# preparedinstruments_0_bechemel_v10_KEYPA.net
KiCad netlist of a schematic drawn in EAGLE
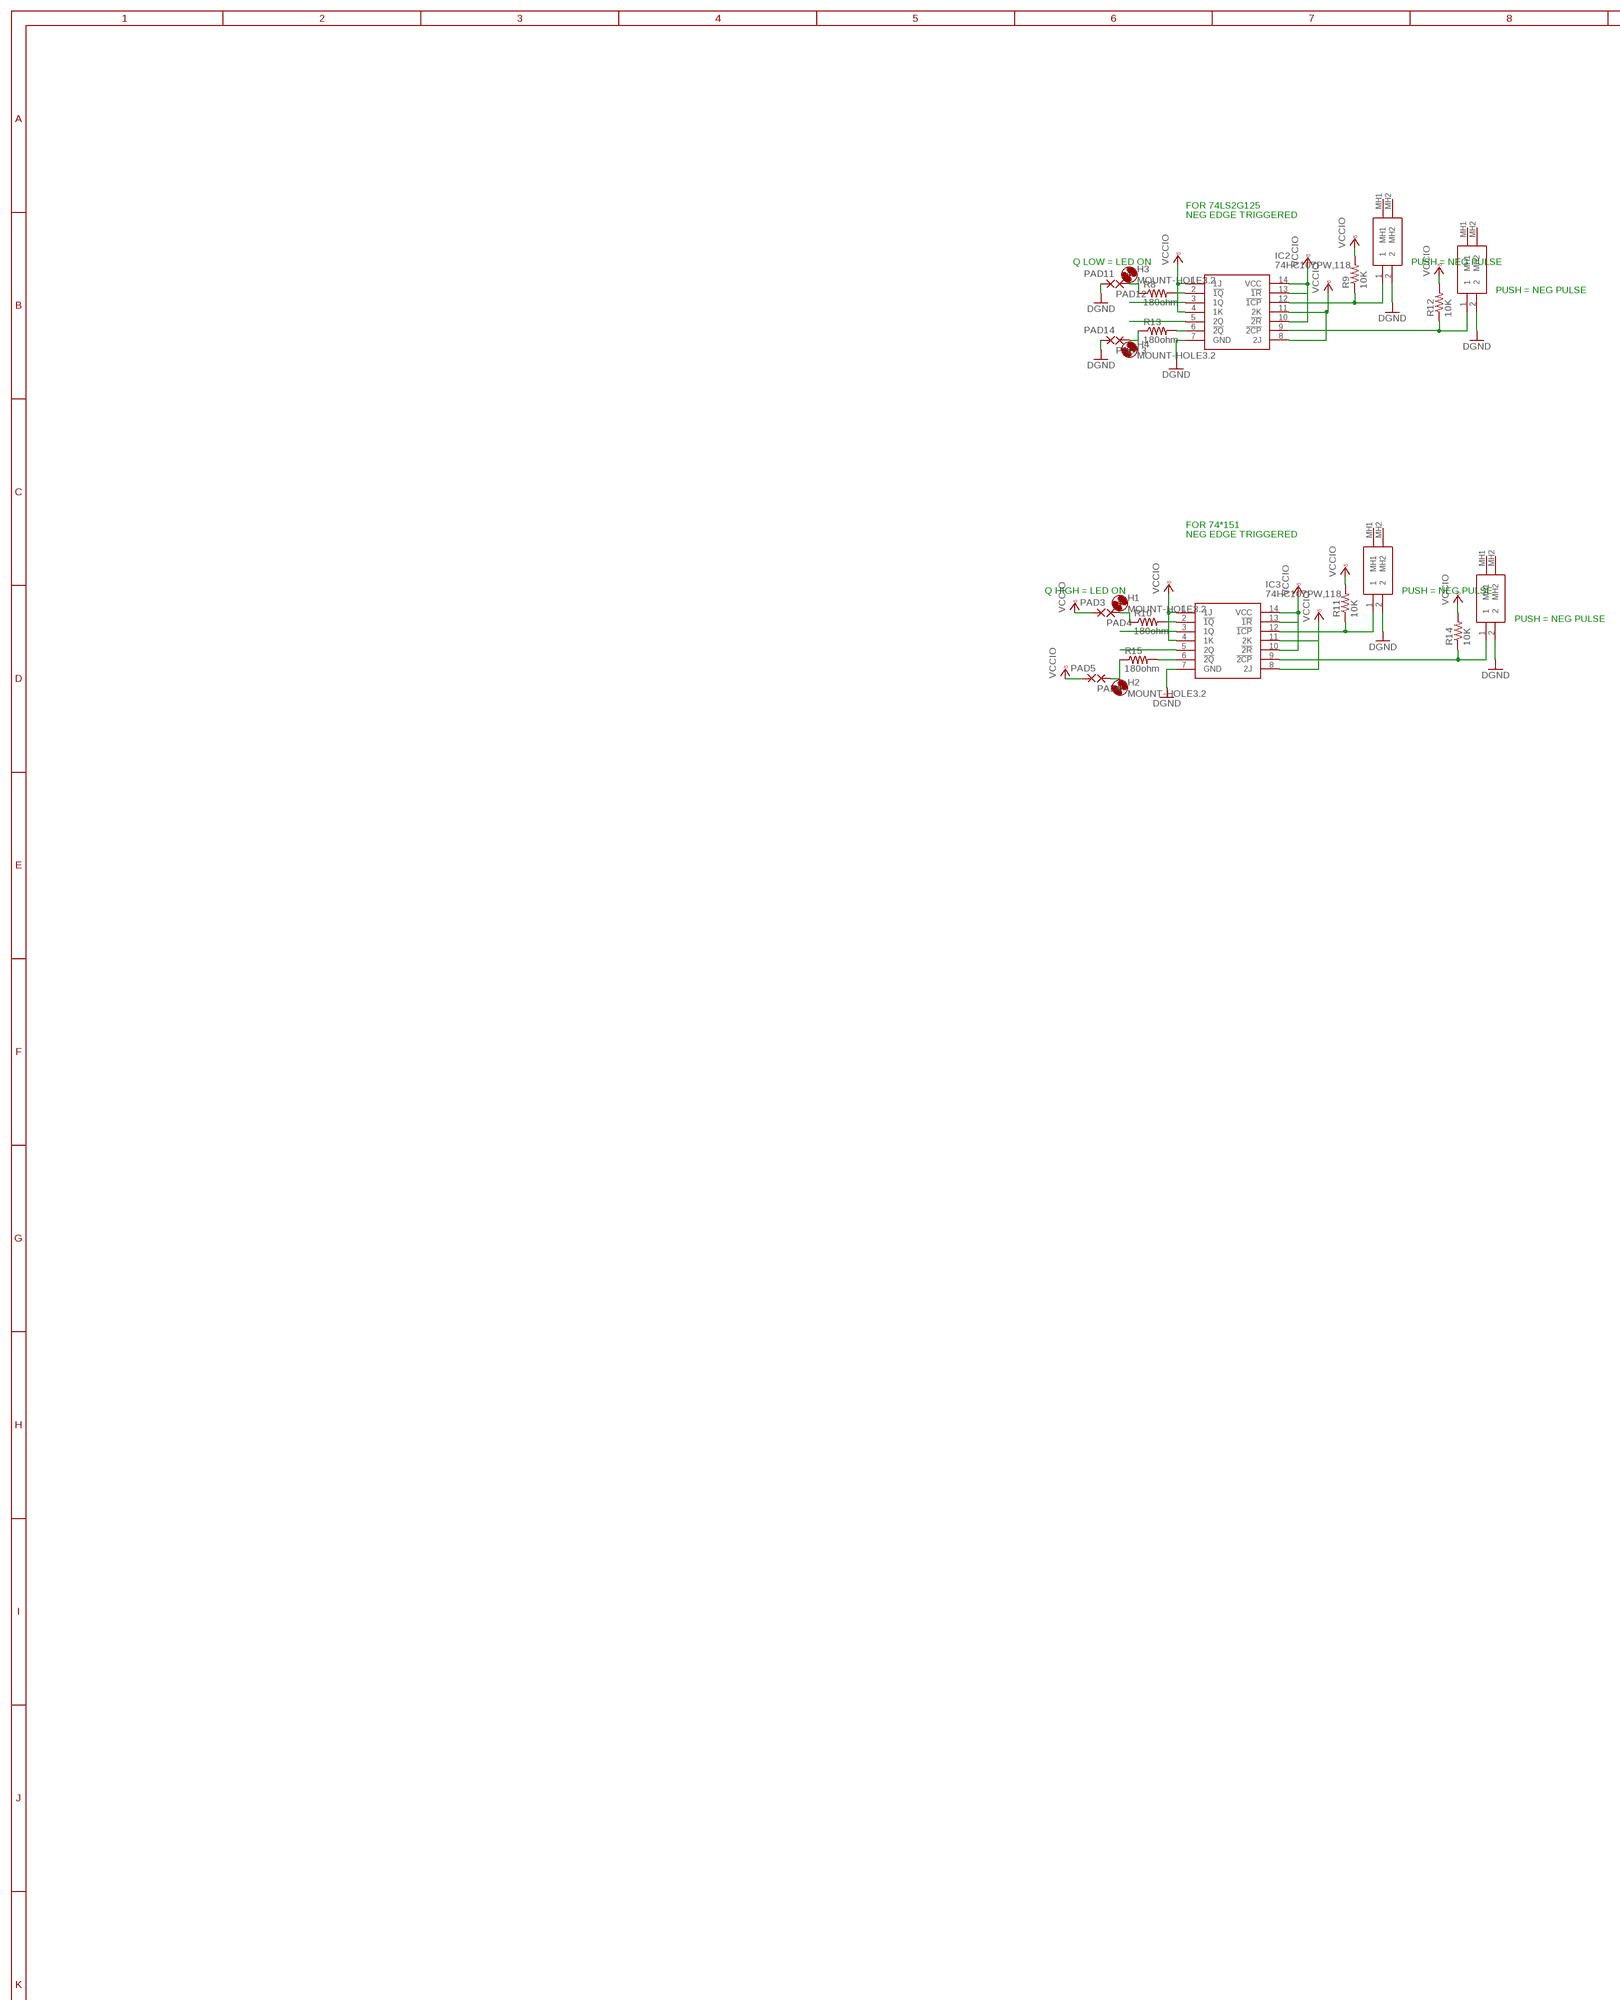
[diagram p0: schematic, sheet 1, part 1 of 3]
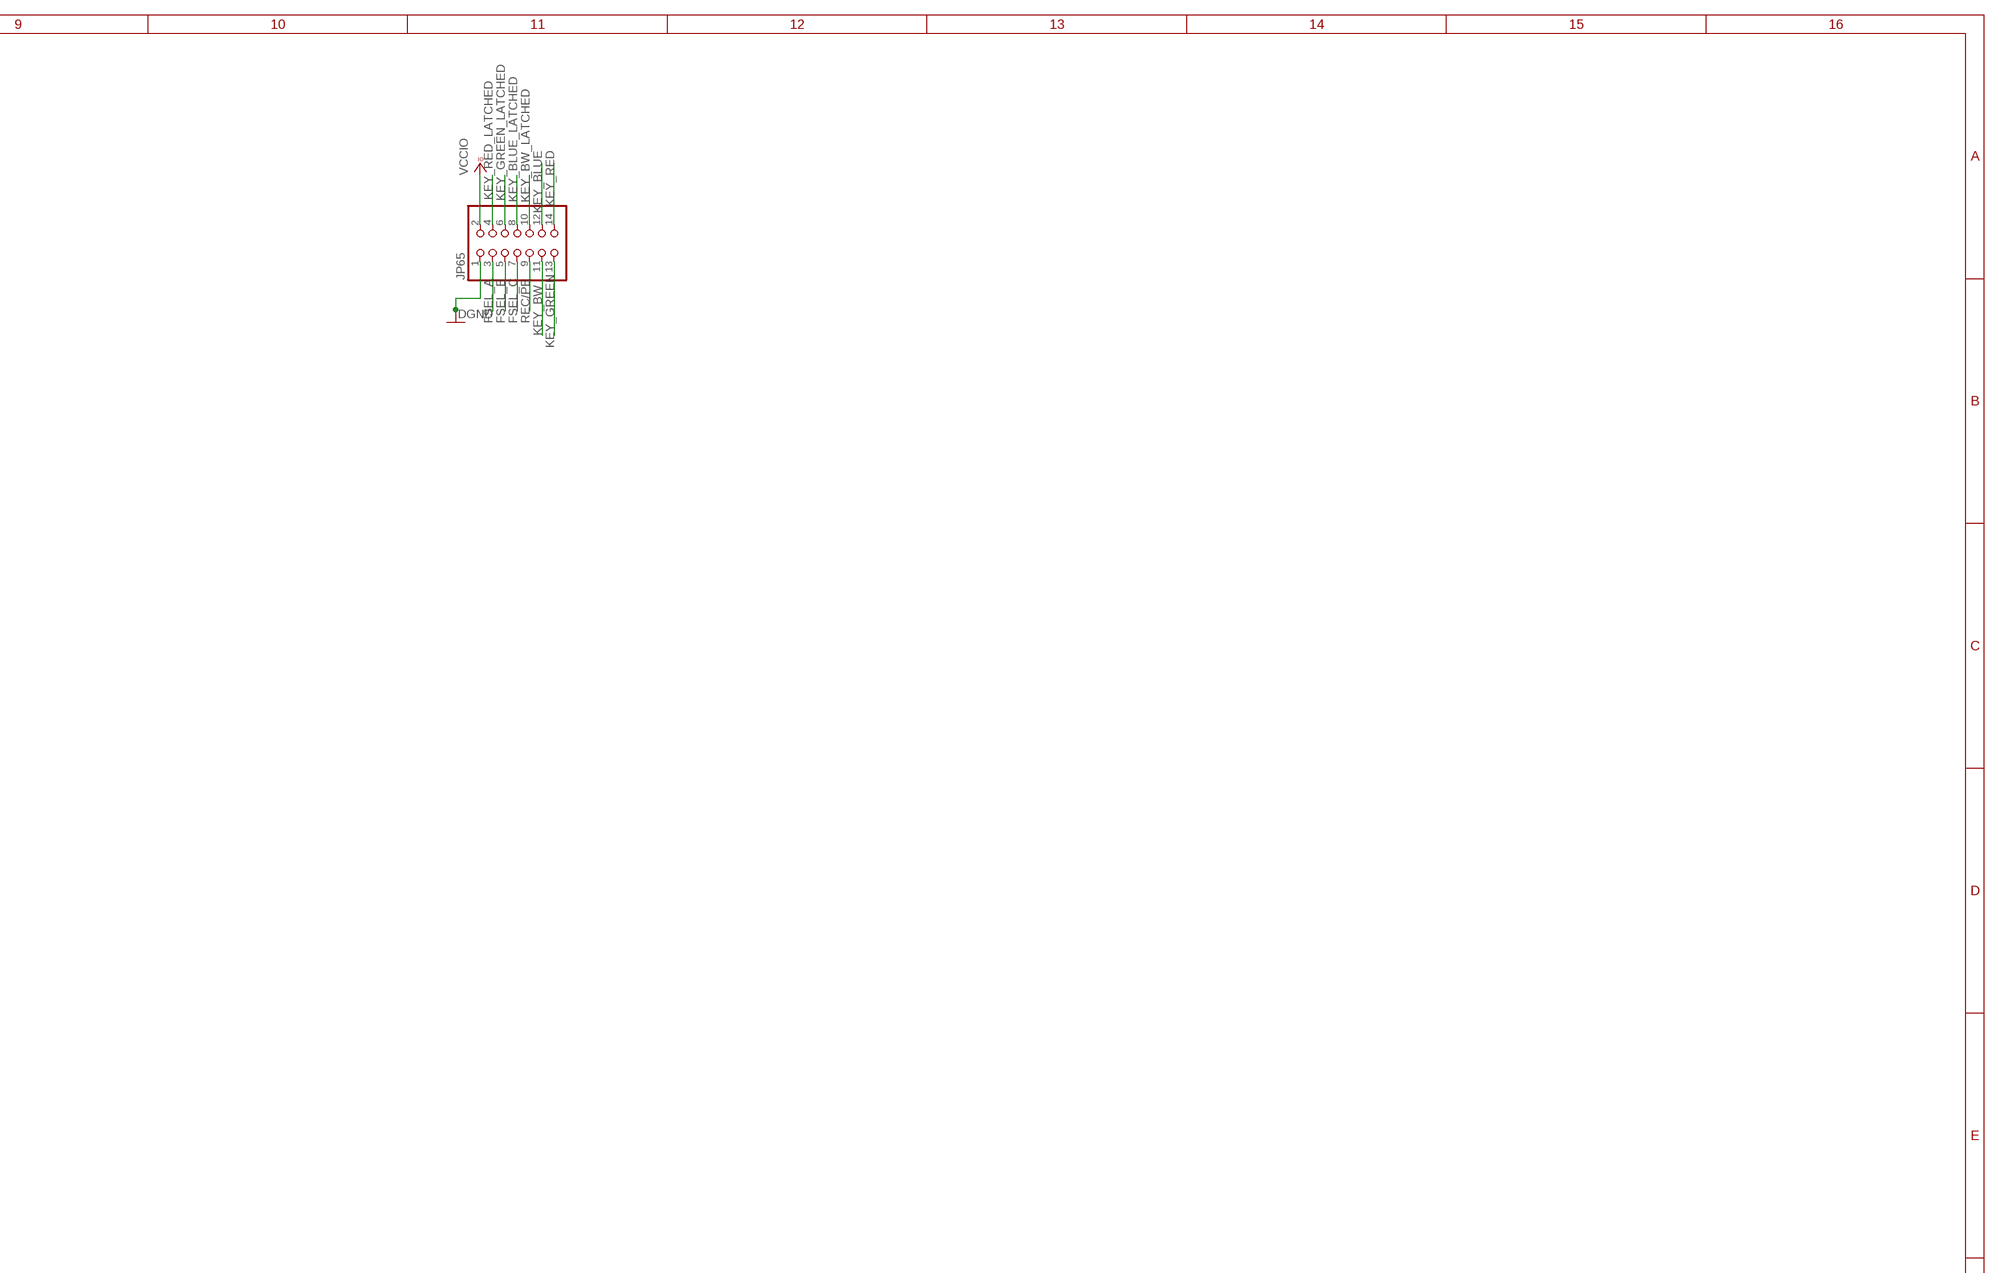
[diagram p1: schematic, sheet 1, part 2 of 3]
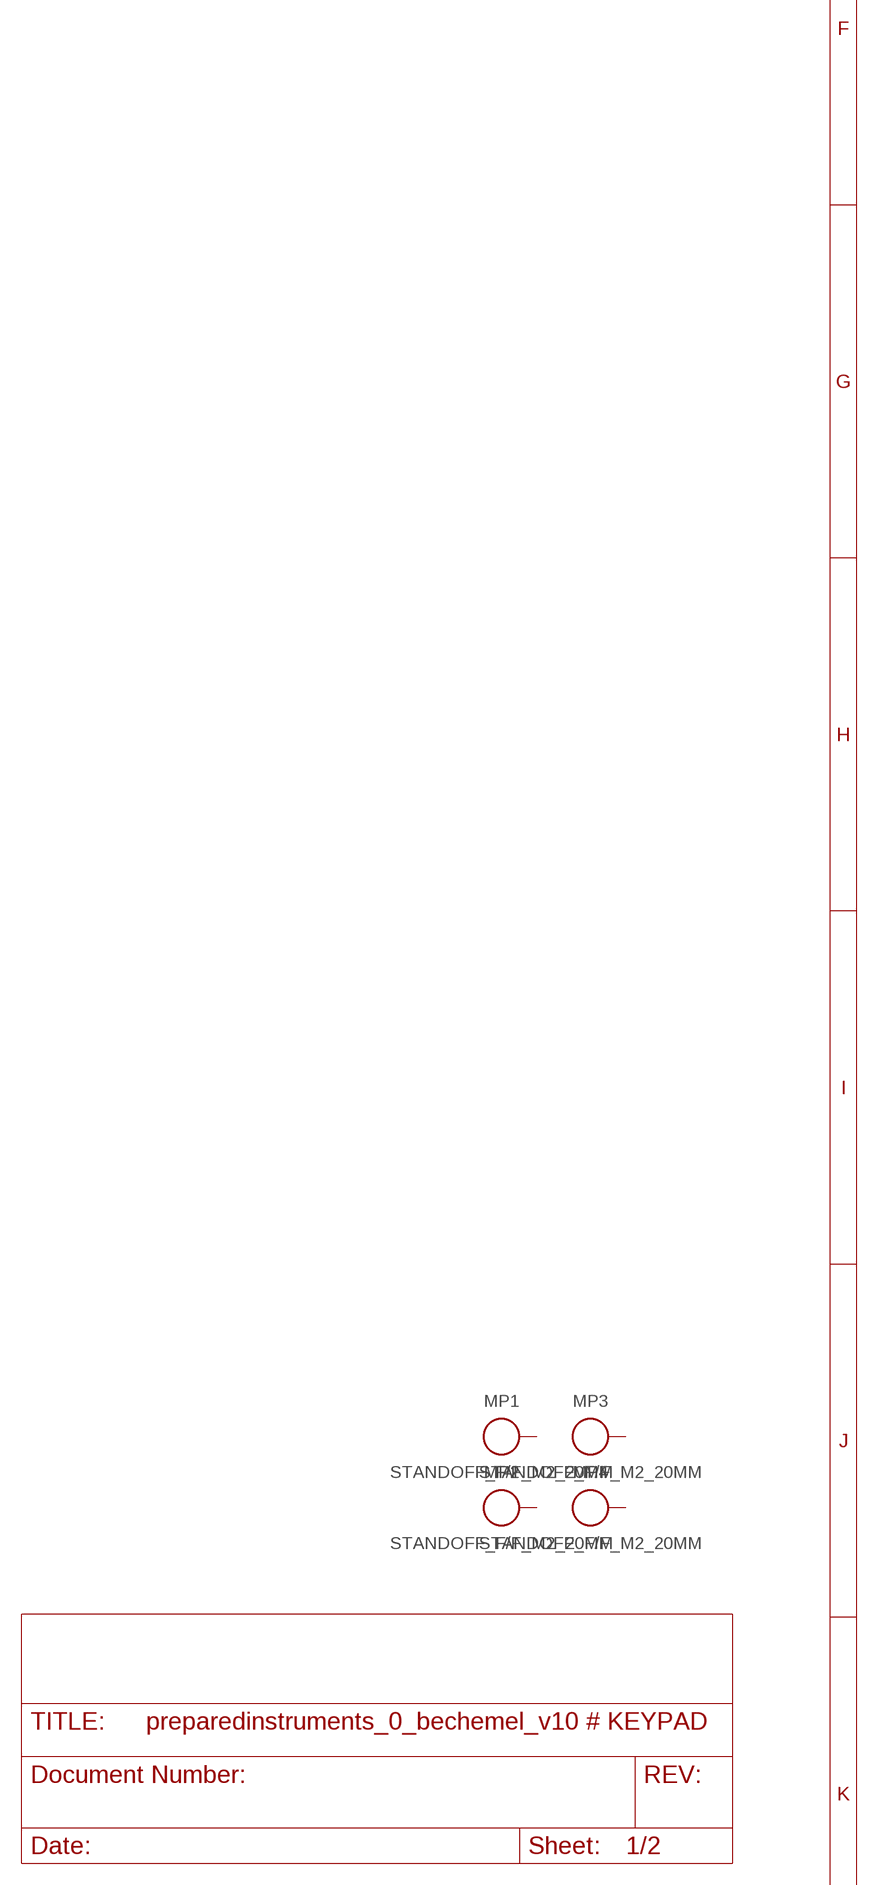
[diagram p2: schematic, sheet 1, part 3 of 3]
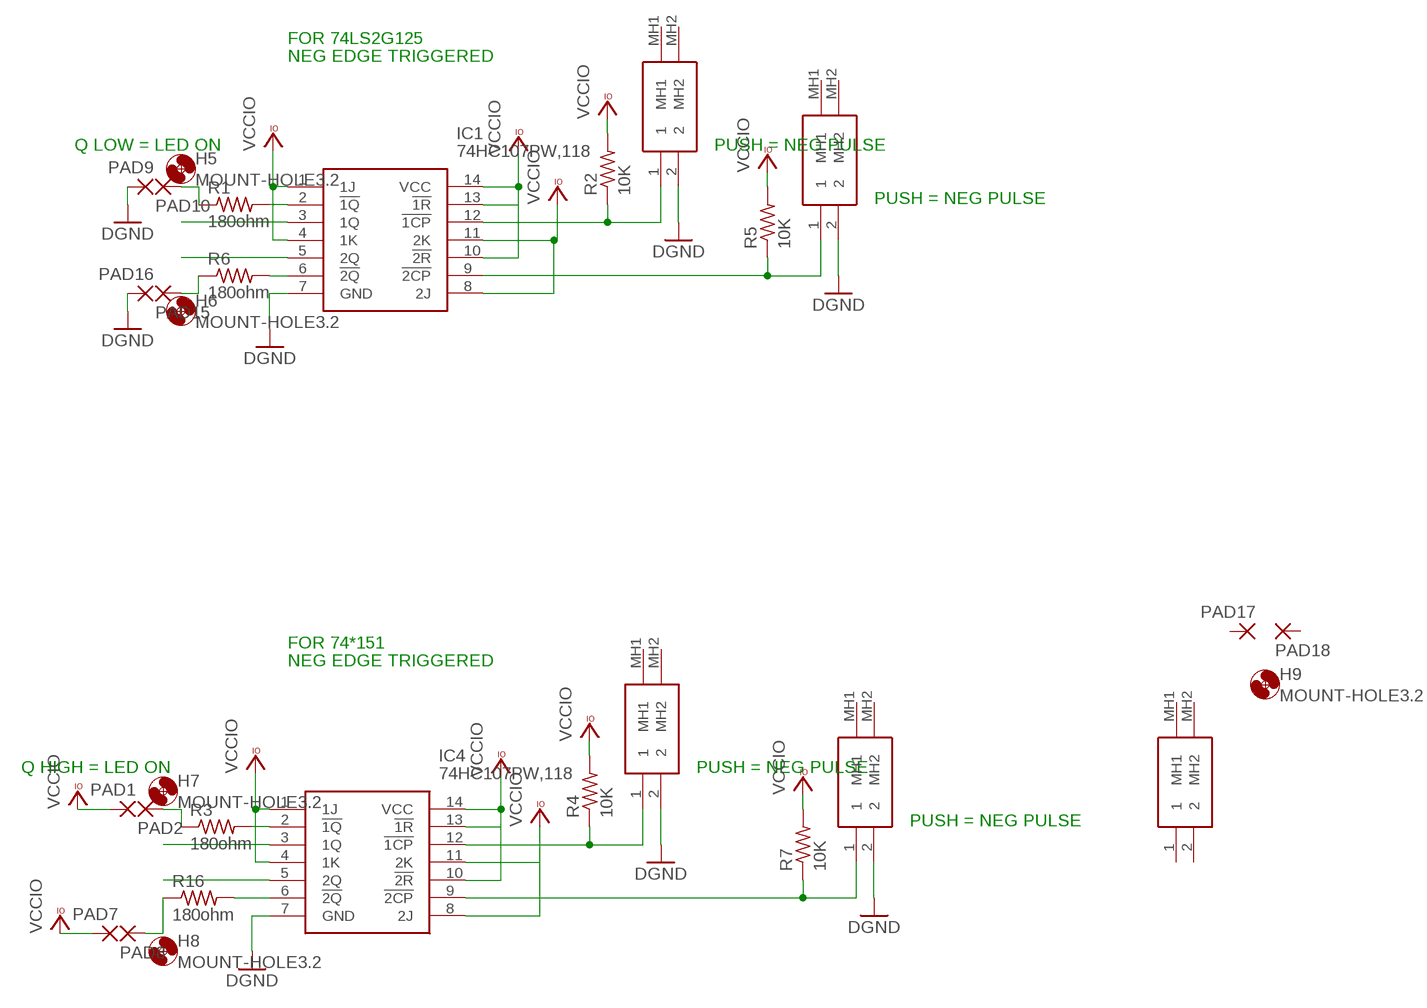
[diagram p3: schematic, sheet 2]

(export (version "E")
  (design (tool "Eeschema 10.0.6"))
  (components
    (comp (ref "H1")
      (value "MOUNT-HOLE3.2")
      (footprint "eagle-import:3,2")
      (libsource (lib "eagle-import") (part "MOUNT-HOLE3.2"))
    )
    (comp (ref "H2")
      (value "MOUNT-HOLE3.2")
      (footprint "eagle-import:3,2")
      (libsource (lib "eagle-import") (part "MOUNT-HOLE3.2"))
    )
    (comp (ref "H3")
      (value "MOUNT-HOLE3.2")
      (footprint "eagle-import:3,2")
      (libsource (lib "eagle-import") (part "MOUNT-HOLE3.2"))
    )
    (comp (ref "H4")
      (value "MOUNT-HOLE3.2")
      (footprint "eagle-import:3,2")
      (libsource (lib "eagle-import") (part "MOUNT-HOLE3.2"))
    )
    (comp (ref "IC2")
      (value "74HC107PW,118")
      (footprint "eagle-import:SOP65P640X110-14N")
      (fields (field (name "MOUSER_PART_NUMBER") "771-HC107PW118"))
      (libsource (lib "eagle-import") (part "74HC107PW,118"))
    )
    (comp (ref "IC3")
      (value "74HC107PW,118")
      (footprint "eagle-import:SOP65P640X110-14N")
      (fields (field (name "MOUSER_PART_NUMBER") "771-HC107PW118"))
      (libsource (lib "eagle-import") (part "74HC107PW,118"))
    )
    (comp (ref "JP65")
      (value "PINHD-2X7")
      (footprint "eagle-import:2X07")
      (libsource (lib "eagle-import") (part "PINHD-2X7"))
    )
    (comp (ref "MP1")
      (value "STANDOFF_F/F_M2_20MM")
      (footprint "eagle-import:STANDOFF_HEX_FEMALE_400X2000_M2X0.4_MTGP600H220")
      (libsource (lib "eagle-import") (part "STANDOFF_F/FM2_20MM_"))
    )
    (comp (ref "MP2")
      (value "STANDOFF_F/F_M2_20MM")
      (footprint "eagle-import:STANDOFF_HEX_FEMALE_400X2000_M2X0.4_MTGP600H220")
      (libsource (lib "eagle-import") (part "STANDOFF_F/FM2_20MM_"))
    )
    (comp (ref "MP3")
      (value "STANDOFF_F/F_M2_20MM")
      (footprint "eagle-import:STANDOFF_HEX_FEMALE_400X2000_M2X0.4_MTGP600H220")
      (libsource (lib "eagle-import") (part "STANDOFF_F/FM2_20MM_"))
    )
    (comp (ref "MP4")
      (value "STANDOFF_F/F_M2_20MM")
      (footprint "eagle-import:STANDOFF_HEX_FEMALE_400X2000_M2X0.4_MTGP600H220")
      (libsource (lib "eagle-import") (part "STANDOFF_F/FM2_20MM_"))
    )
    (comp (ref "PAD3")
      (value "SMD2")
      (footprint "eagle-import:SMD1,27-2,54")
      (libsource (lib "eagle-import") (part "SMD2"))
    )
    (comp (ref "PAD4")
      (value "SMD2")
      (footprint "eagle-import:SMD1,27-2,54")
      (libsource (lib "eagle-import") (part "SMD2"))
    )
    (comp (ref "PAD5")
      (value "SMD2")
      (footprint "eagle-import:SMD1,27-2,54")
      (libsource (lib "eagle-import") (part "SMD2"))
    )
    (comp (ref "PAD6")
      (value "SMD2")
      (footprint "eagle-import:SMD1,27-2,54")
      (libsource (lib "eagle-import") (part "SMD2"))
    )
    (comp (ref "PAD11")
      (value "SMD2")
      (footprint "eagle-import:SMD1,27-2,54")
      (libsource (lib "eagle-import") (part "SMD2"))
    )
    (comp (ref "PAD12")
      (value "SMD2")
      (footprint "eagle-import:SMD1,27-2,54")
      (libsource (lib "eagle-import") (part "SMD2"))
    )
    (comp (ref "PAD13")
      (value "SMD2")
      (footprint "eagle-import:SMD1,27-2,54")
      (libsource (lib "eagle-import") (part "SMD2"))
    )
    (comp (ref "PAD14")
      (value "SMD2")
      (footprint "eagle-import:SMD1,27-2,54")
      (libsource (lib "eagle-import") (part "SMD2"))
    )
    (comp (ref "R8")
      (value "180ohm")
      (footprint "eagle-import:R0805")
      (libsource (lib "eagle-import") (part "R-US_R0805"))
    )
    (comp (ref "R9")
      (value "10K")
      (footprint "eagle-import:R0805")
      (libsource (lib "eagle-import") (part "R-US_R0805"))
    )
    (comp (ref "R10")
      (value "180ohm")
      (footprint "eagle-import:R0805")
      (libsource (lib "eagle-import") (part "R-US_R0805"))
    )
    (comp (ref "R11")
      (value "10K")
      (footprint "eagle-import:R0805")
      (libsource (lib "eagle-import") (part "R-US_R0805"))
    )
    (comp (ref "R12")
      (value "10K")
      (footprint "eagle-import:R0805")
      (libsource (lib "eagle-import") (part "R-US_R0805"))
    )
    (comp (ref "R13")
      (value "180ohm")
      (footprint "eagle-import:R0805")
      (libsource (lib "eagle-import") (part "R-US_R0805"))
    )
    (comp (ref "R14")
      (value "10K")
      (footprint "eagle-import:R0805")
      (libsource (lib "eagle-import") (part "R-US_R0805"))
    )
    (comp (ref "R15")
      (value "180ohm")
      (footprint "eagle-import:R0805")
      (libsource (lib "eagle-import") (part "R-US_R0805"))
    )
    (comp (ref "S6")
      (value "MX1A-11NW")
      (footprint "eagle-import:MX1A11NW")
      (fields (field (name "MOUSER_PART_NUMBER") "540-MX1A-11NW"))
      (libsource (lib "eagle-import") (part "MX1A-11NW"))
    )
    (comp (ref "S7")
      (value "MX1A-11NW")
      (footprint "eagle-import:MX1A11NW")
      (fields (field (name "MOUSER_PART_NUMBER") "540-MX1A-11NW"))
      (libsource (lib "eagle-import") (part "MX1A-11NW"))
    )
    (comp (ref "S8")
      (value "MX1A-11NW")
      (footprint "eagle-import:MX1A11NW")
      (fields (field (name "MOUSER_PART_NUMBER") "540-MX1A-11NW"))
      (libsource (lib "eagle-import") (part "MX1A-11NW"))
    )
    (comp (ref "S9")
      (value "MX1A-11NW")
      (footprint "eagle-import:MX1A11NW")
      (fields (field (name "MOUSER_PART_NUMBER") "540-MX1A-11NW"))
      (libsource (lib "eagle-import") (part "MX1A-11NW"))
    )
    (comp (ref "H5")
      (value "MOUNT-HOLE3.2")
      (footprint "eagle-import:3,2")
      (libsource (lib "eagle-import") (part "MOUNT-HOLE3.2"))
    )
    (comp (ref "H6")
      (value "MOUNT-HOLE3.2")
      (footprint "eagle-import:3,2")
      (libsource (lib "eagle-import") (part "MOUNT-HOLE3.2"))
    )
    (comp (ref "H7")
      (value "MOUNT-HOLE3.2")
      (footprint "eagle-import:3,2")
      (libsource (lib "eagle-import") (part "MOUNT-HOLE3.2"))
    )
    (comp (ref "H8")
      (value "MOUNT-HOLE3.2")
      (footprint "eagle-import:3,2")
      (libsource (lib "eagle-import") (part "MOUNT-HOLE3.2"))
    )
    (comp (ref "H9")
      (value "MOUNT-HOLE3.2")
      (footprint "eagle-import:3,2")
      (libsource (lib "eagle-import") (part "MOUNT-HOLE3.2"))
    )
    (comp (ref "IC1")
      (value "74HC107PW,118")
      (footprint "eagle-import:SOP65P640X110-14N")
      (fields (field (name "MOUSER_PART_NUMBER") "771-HC107PW118"))
      (libsource (lib "eagle-import") (part "74HC107PW,118"))
    )
    (comp (ref "IC4")
      (value "74HC107PW,118")
      (footprint "eagle-import:SOP65P640X110-14N")
      (fields (field (name "MOUSER_PART_NUMBER") "771-HC107PW118"))
      (libsource (lib "eagle-import") (part "74HC107PW,118"))
    )
    (comp (ref "PAD1")
      (value "SMD2")
      (footprint "eagle-import:SMD1,27-2,54")
      (libsource (lib "eagle-import") (part "SMD2"))
    )
    (comp (ref "PAD2")
      (value "SMD2")
      (footprint "eagle-import:SMD1,27-2,54")
      (libsource (lib "eagle-import") (part "SMD2"))
    )
    (comp (ref "PAD7")
      (value "SMD2")
      (footprint "eagle-import:SMD1,27-2,54")
      (libsource (lib "eagle-import") (part "SMD2"))
    )
    (comp (ref "PAD8")
      (value "SMD2")
      (footprint "eagle-import:SMD1,27-2,54")
      (libsource (lib "eagle-import") (part "SMD2"))
    )
    (comp (ref "PAD9")
      (value "SMD2")
      (footprint "eagle-import:SMD1,27-2,54")
      (libsource (lib "eagle-import") (part "SMD2"))
    )
    (comp (ref "PAD10")
      (value "SMD2")
      (footprint "eagle-import:SMD1,27-2,54")
      (libsource (lib "eagle-import") (part "SMD2"))
    )
    (comp (ref "PAD15")
      (value "SMD2")
      (footprint "eagle-import:SMD1,27-2,54")
      (libsource (lib "eagle-import") (part "SMD2"))
    )
    (comp (ref "PAD16")
      (value "SMD2")
      (footprint "eagle-import:SMD1,27-2,54")
      (libsource (lib "eagle-import") (part "SMD2"))
    )
    (comp (ref "PAD17")
      (value "SMD2")
      (footprint "eagle-import:SMD1,27-2,54")
      (libsource (lib "eagle-import") (part "SMD2"))
    )
    (comp (ref "PAD18")
      (value "SMD2")
      (footprint "eagle-import:SMD1,27-2,54")
      (libsource (lib "eagle-import") (part "SMD2"))
    )
    (comp (ref "R1")
      (value "180ohm")
      (footprint "eagle-import:R0805")
      (libsource (lib "eagle-import") (part "R-US_R0805"))
    )
    (comp (ref "R2")
      (value "10K")
      (footprint "eagle-import:R0805")
      (libsource (lib "eagle-import") (part "R-US_R0805"))
    )
    (comp (ref "R3")
      (value "180ohm")
      (footprint "eagle-import:R0805")
      (libsource (lib "eagle-import") (part "R-US_R0805"))
    )
    (comp (ref "R4")
      (value "10K")
      (footprint "eagle-import:R0805")
      (libsource (lib "eagle-import") (part "R-US_R0805"))
    )
    (comp (ref "R5")
      (value "10K")
      (footprint "eagle-import:R0805")
      (libsource (lib "eagle-import") (part "R-US_R0805"))
    )
    (comp (ref "R6")
      (value "180ohm")
      (footprint "eagle-import:R0805")
      (libsource (lib "eagle-import") (part "R-US_R0805"))
    )
    (comp (ref "R7")
      (value "10K")
      (footprint "eagle-import:R0805")
      (libsource (lib "eagle-import") (part "R-US_R0805"))
    )
    (comp (ref "R16")
      (value "180ohm")
      (footprint "eagle-import:R0805")
      (libsource (lib "eagle-import") (part "R-US_R0805"))
    )
    (comp (ref "S1")
      (value "MX1A-11NW")
      (footprint "eagle-import:MX1A11NW")
      (fields (field (name "MOUSER_PART_NUMBER") "540-MX1A-11NW"))
      (libsource (lib "eagle-import") (part "MX1A-11NW"))
    )
    (comp (ref "S2")
      (value "MX1A-11NW")
      (footprint "eagle-import:MX1A11NW")
      (fields (field (name "MOUSER_PART_NUMBER") "540-MX1A-11NW"))
      (libsource (lib "eagle-import") (part "MX1A-11NW"))
    )
    (comp (ref "S3")
      (value "MX1A-11NW")
      (footprint "eagle-import:MX1A11NW")
      (fields (field (name "MOUSER_PART_NUMBER") "540-MX1A-11NW"))
      (libsource (lib "eagle-import") (part "MX1A-11NW"))
    )
    (comp (ref "S4")
      (value "MX1A-11NW")
      (footprint "eagle-import:MX1A11NW")
      (fields (field (name "MOUSER_PART_NUMBER") "540-MX1A-11NW"))
      (libsource (lib "eagle-import") (part "MX1A-11NW"))
    )
    (comp (ref "S5")
      (value "MX1A-11NW")
      (footprint "eagle-import:MX1A11NW")
      (fields (field (name "MOUSER_PART_NUMBER") "540-MX1A-11NW"))
      (libsource (lib "eagle-import") (part "MX1A-11NW"))
    )
  )
  (nets
    (net (code "1") (name "DGND") (class "Default")
      (node (ref "IC1") (pin "7") (pinfunction "GND_7") (pintype "bidirectional"))
      (node (ref "IC2") (pin "7") (pinfunction "GND_7") (pintype "bidirectional"))
      (node (ref "IC3") (pin "7") (pinfunction "GND_7") (pintype "bidirectional"))
      (node (ref "IC4") (pin "7") (pinfunction "GND_7") (pintype "bidirectional"))
      (node (ref "JP65") (pin "1") (pinfunction "1_1") (pintype "passive"))
      (node (ref "PAD11") (pin "1") (pinfunction "P_1") (pintype "passive"))
      (node (ref "PAD14") (pin "1") (pinfunction "P_1") (pintype "passive"))
      (node (ref "PAD16") (pin "1") (pinfunction "P_1") (pintype "passive"))
      (node (ref "PAD9") (pin "1") (pinfunction "P_1") (pintype "passive"))
      (node (ref "S1") (pin "2") (pinfunction "2_2") (pintype "bidirectional"))
      (node (ref "S2") (pin "2") (pinfunction "2_2") (pintype "bidirectional"))
      (node (ref "S3") (pin "2") (pinfunction "2_2") (pintype "bidirectional"))
      (node (ref "S4") (pin "2") (pinfunction "2_2") (pintype "bidirectional"))
      (node (ref "S6") (pin "2") (pinfunction "2_2") (pintype "bidirectional"))
      (node (ref "S7") (pin "2") (pinfunction "2_2") (pintype "bidirectional"))
      (node (ref "S8") (pin "2") (pinfunction "2_2") (pintype "bidirectional"))
      (node (ref "S9") (pin "2") (pinfunction "2_2") (pintype "bidirectional"))
    )
    (net (code "2") (name "FSEL_A") (class "Default")
      (node (ref "JP65") (pin "3") (pinfunction "3_3") (pintype "passive"))
    )
    (net (code "3") (name "FSEL_B") (class "Default")
      (node (ref "JP65") (pin "5") (pinfunction "5_5") (pintype "passive"))
    )
    (net (code "4") (name "FSEL_C") (class "Default")
      (node (ref "JP65") (pin "7") (pinfunction "7_7") (pintype "passive"))
    )
    (net (code "5") (name "KEY_BLUE") (class "Default")
      (node (ref "JP65") (pin "12") (pinfunction "12_12") (pintype "passive"))
    )
    (net (code "6") (name "KEY_BLUE_LATCHED") (class "Default")
      (node (ref "JP65") (pin "8") (pinfunction "8_8") (pintype "passive"))
    )
    (net (code "7") (name "KEY_BW") (class "Default")
      (node (ref "JP65") (pin "11") (pinfunction "11_11") (pintype "passive"))
    )
    (net (code "8") (name "KEY_BW_LATCHED") (class "Default")
      (node (ref "JP65") (pin "10") (pinfunction "10_10") (pintype "passive"))
    )
    (net (code "9") (name "KEY_GREEN") (class "Default")
      (node (ref "JP65") (pin "13") (pinfunction "13_13") (pintype "passive"))
    )
    (net (code "10") (name "KEY_GREEN_LATCHED") (class "Default")
      (node (ref "JP65") (pin "6") (pinfunction "6_6") (pintype "passive"))
    )
    (net (code "11") (name "KEY_RED") (class "Default")
      (node (ref "JP65") (pin "14") (pinfunction "14_14") (pintype "passive"))
    )
    (net (code "12") (name "KEY_RED_LATCHED") (class "Default")
      (node (ref "JP65") (pin "4") (pinfunction "4_4") (pintype "passive"))
    )
    (net (code "13") (name "Net-(IC1-~{1CP})") (class "Default")
      (node (ref "IC1") (pin "12") (pinfunction "~{1CP}_12") (pintype "bidirectional"))
      (node (ref "R2") (pin "1") (pinfunction "1_1") (pintype "passive"))
      (node (ref "S1") (pin "1") (pinfunction "1_1") (pintype "bidirectional"))
    )
    (net (code "14") (name "Net-(IC1-~{1Q})") (class "Default")
      (node (ref "IC1") (pin "2") (pinfunction "~{1Q}_2") (pintype "bidirectional"))
      (node (ref "R1") (pin "2") (pinfunction "2_2") (pintype "passive"))
    )
    (net (code "15") (name "Net-(IC1-~{2CP})") (class "Default")
      (node (ref "IC1") (pin "9") (pinfunction "~{2CP}_9") (pintype "bidirectional"))
      (node (ref "R5") (pin "1") (pinfunction "1_1") (pintype "passive"))
      (node (ref "S3") (pin "1") (pinfunction "1_1") (pintype "bidirectional"))
    )
    (net (code "16") (name "Net-(IC1-~{2Q})") (class "Default")
      (node (ref "IC1") (pin "6") (pinfunction "~{2Q}_6") (pintype "bidirectional"))
      (node (ref "R6") (pin "2") (pinfunction "2_2") (pintype "passive"))
    )
    (net (code "17") (name "Net-(IC2-~{1CP})") (class "Default")
      (node (ref "IC2") (pin "12") (pinfunction "~{1CP}_12") (pintype "bidirectional"))
      (node (ref "R9") (pin "1") (pinfunction "1_1") (pintype "passive"))
      (node (ref "S6") (pin "1") (pinfunction "1_1") (pintype "bidirectional"))
    )
    (net (code "18") (name "Net-(IC2-~{1Q})") (class "Default")
      (node (ref "IC2") (pin "2") (pinfunction "~{1Q}_2") (pintype "bidirectional"))
      (node (ref "R8") (pin "2") (pinfunction "2_2") (pintype "passive"))
    )
    (net (code "19") (name "Net-(IC2-~{2CP})") (class "Default")
      (node (ref "IC2") (pin "9") (pinfunction "~{2CP}_9") (pintype "bidirectional"))
      (node (ref "R12") (pin "1") (pinfunction "1_1") (pintype "passive"))
      (node (ref "S8") (pin "1") (pinfunction "1_1") (pintype "bidirectional"))
    )
    (net (code "20") (name "Net-(IC2-~{2Q})") (class "Default")
      (node (ref "IC2") (pin "6") (pinfunction "~{2Q}_6") (pintype "bidirectional"))
      (node (ref "R13") (pin "2") (pinfunction "2_2") (pintype "passive"))
    )
    (net (code "21") (name "Net-(IC3-~{1CP})") (class "Default")
      (node (ref "IC3") (pin "12") (pinfunction "~{1CP}_12") (pintype "bidirectional"))
      (node (ref "R11") (pin "1") (pinfunction "1_1") (pintype "passive"))
      (node (ref "S7") (pin "1") (pinfunction "1_1") (pintype "bidirectional"))
    )
    (net (code "22") (name "Net-(IC3-~{1Q})") (class "Default")
      (node (ref "IC3") (pin "2") (pinfunction "~{1Q}_2") (pintype "bidirectional"))
      (node (ref "R10") (pin "2") (pinfunction "2_2") (pintype "passive"))
    )
    (net (code "23") (name "Net-(IC3-~{2CP})") (class "Default")
      (node (ref "IC3") (pin "9") (pinfunction "~{2CP}_9") (pintype "bidirectional"))
      (node (ref "R14") (pin "1") (pinfunction "1_1") (pintype "passive"))
      (node (ref "S9") (pin "1") (pinfunction "1_1") (pintype "bidirectional"))
    )
    (net (code "24") (name "Net-(IC3-~{2Q})") (class "Default")
      (node (ref "IC3") (pin "6") (pinfunction "~{2Q}_6") (pintype "bidirectional"))
      (node (ref "R15") (pin "2") (pinfunction "2_2") (pintype "passive"))
    )
    (net (code "25") (name "Net-(IC4-~{1CP})") (class "Default")
      (node (ref "IC4") (pin "12") (pinfunction "~{1CP}_12") (pintype "bidirectional"))
      (node (ref "R4") (pin "1") (pinfunction "1_1") (pintype "passive"))
      (node (ref "S2") (pin "1") (pinfunction "1_1") (pintype "bidirectional"))
    )
    (net (code "26") (name "Net-(IC4-~{1Q})") (class "Default")
      (node (ref "IC4") (pin "2") (pinfunction "~{1Q}_2") (pintype "bidirectional"))
      (node (ref "R3") (pin "2") (pinfunction "2_2") (pintype "passive"))
    )
    (net (code "27") (name "Net-(IC4-~{2CP})") (class "Default")
      (node (ref "IC4") (pin "9") (pinfunction "~{2CP}_9") (pintype "bidirectional"))
      (node (ref "R7") (pin "1") (pinfunction "1_1") (pintype "passive"))
      (node (ref "S4") (pin "1") (pinfunction "1_1") (pintype "bidirectional"))
    )
    (net (code "28") (name "Net-(IC4-~{2Q})") (class "Default")
      (node (ref "IC4") (pin "6") (pinfunction "~{2Q}_6") (pintype "bidirectional"))
      (node (ref "R16") (pin "2") (pinfunction "2_2") (pintype "passive"))
    )
    (net (code "29") (name "Net-(PAD2-P)") (class "Default")
      (node (ref "PAD2") (pin "1") (pinfunction "P_1") (pintype "passive"))
      (node (ref "R3") (pin "1") (pinfunction "1_1") (pintype "passive"))
    )
    (net (code "30") (name "Net-(PAD4-P)") (class "Default")
      (node (ref "PAD4") (pin "1") (pinfunction "P_1") (pintype "passive"))
      (node (ref "R10") (pin "1") (pinfunction "1_1") (pintype "passive"))
    )
    (net (code "31") (name "Net-(PAD6-P)") (class "Default")
      (node (ref "PAD6") (pin "1") (pinfunction "P_1") (pintype "passive"))
      (node (ref "R15") (pin "1") (pinfunction "1_1") (pintype "passive"))
    )
    (net (code "32") (name "Net-(PAD8-P)") (class "Default")
      (node (ref "PAD8") (pin "1") (pinfunction "P_1") (pintype "passive"))
      (node (ref "R16") (pin "1") (pinfunction "1_1") (pintype "passive"))
    )
    (net (code "33") (name "Net-(PAD10-P)") (class "Default")
      (node (ref "PAD10") (pin "1") (pinfunction "P_1") (pintype "passive"))
      (node (ref "R1") (pin "1") (pinfunction "1_1") (pintype "passive"))
    )
    (net (code "34") (name "Net-(PAD12-P)") (class "Default")
      (node (ref "PAD12") (pin "1") (pinfunction "P_1") (pintype "passive"))
      (node (ref "R8") (pin "1") (pinfunction "1_1") (pintype "passive"))
    )
    (net (code "35") (name "Net-(PAD13-P)") (class "Default")
      (node (ref "PAD13") (pin "1") (pinfunction "P_1") (pintype "passive"))
      (node (ref "R13") (pin "1") (pinfunction "1_1") (pintype "passive"))
    )
    (net (code "36") (name "Net-(PAD15-P)") (class "Default")
      (node (ref "PAD15") (pin "1") (pinfunction "P_1") (pintype "passive"))
      (node (ref "R6") (pin "1") (pinfunction "1_1") (pintype "passive"))
    )
    (net (code "37") (name "REC{slash}PB") (class "Default")
      (node (ref "JP65") (pin "9") (pinfunction "9_9") (pintype "passive"))
    )
    (net (code "38") (name "VCCIO") (class "Default")
      (node (ref "IC1") (pin "1") (pinfunction "1J_1") (pintype "bidirectional"))
      (node (ref "IC1") (pin "10") (pinfunction "~{2R}_10") (pintype "bidirectional"))
      (node (ref "IC1") (pin "11") (pinfunction "2K_11") (pintype "bidirectional"))
      (node (ref "IC1") (pin "13") (pinfunction "~{1R}_13") (pintype "bidirectional"))
      (node (ref "IC1") (pin "14") (pinfunction "VCC_14") (pintype "bidirectional"))
      (node (ref "IC1") (pin "4") (pinfunction "1K_4") (pintype "bidirectional"))
      (node (ref "IC1") (pin "8") (pinfunction "2J_8") (pintype "bidirectional"))
      (node (ref "IC2") (pin "1") (pinfunction "1J_1") (pintype "bidirectional"))
      (node (ref "IC2") (pin "10") (pinfunction "~{2R}_10") (pintype "bidirectional"))
      (node (ref "IC2") (pin "11") (pinfunction "2K_11") (pintype "bidirectional"))
      (node (ref "IC2") (pin "13") (pinfunction "~{1R}_13") (pintype "bidirectional"))
      (node (ref "IC2") (pin "14") (pinfunction "VCC_14") (pintype "bidirectional"))
      (node (ref "IC2") (pin "4") (pinfunction "1K_4") (pintype "bidirectional"))
      (node (ref "IC2") (pin "8") (pinfunction "2J_8") (pintype "bidirectional"))
      (node (ref "IC3") (pin "1") (pinfunction "1J_1") (pintype "bidirectional"))
      (node (ref "IC3") (pin "10") (pinfunction "~{2R}_10") (pintype "bidirectional"))
      (node (ref "IC3") (pin "11") (pinfunction "2K_11") (pintype "bidirectional"))
      (node (ref "IC3") (pin "13") (pinfunction "~{1R}_13") (pintype "bidirectional"))
      (node (ref "IC3") (pin "14") (pinfunction "VCC_14") (pintype "bidirectional"))
      (node (ref "IC3") (pin "4") (pinfunction "1K_4") (pintype "bidirectional"))
      (node (ref "IC3") (pin "8") (pinfunction "2J_8") (pintype "bidirectional"))
      (node (ref "IC4") (pin "1") (pinfunction "1J_1") (pintype "bidirectional"))
      (node (ref "IC4") (pin "10") (pinfunction "~{2R}_10") (pintype "bidirectional"))
      (node (ref "IC4") (pin "11") (pinfunction "2K_11") (pintype "bidirectional"))
      (node (ref "IC4") (pin "13") (pinfunction "~{1R}_13") (pintype "bidirectional"))
      (node (ref "IC4") (pin "14") (pinfunction "VCC_14") (pintype "bidirectional"))
      (node (ref "IC4") (pin "4") (pinfunction "1K_4") (pintype "bidirectional"))
      (node (ref "IC4") (pin "8") (pinfunction "2J_8") (pintype "bidirectional"))
      (node (ref "JP65") (pin "2") (pinfunction "2_2") (pintype "passive"))
      (node (ref "PAD1") (pin "1") (pinfunction "P_1") (pintype "passive"))
      (node (ref "PAD3") (pin "1") (pinfunction "P_1") (pintype "passive"))
      (node (ref "PAD5") (pin "1") (pinfunction "P_1") (pintype "passive"))
      (node (ref "PAD7") (pin "1") (pinfunction "P_1") (pintype "passive"))
      (node (ref "R11") (pin "2") (pinfunction "2_2") (pintype "passive"))
      (node (ref "R12") (pin "2") (pinfunction "2_2") (pintype "passive"))
      (node (ref "R14") (pin "2") (pinfunction "2_2") (pintype "passive"))
      (node (ref "R2") (pin "2") (pinfunction "2_2") (pintype "passive"))
      (node (ref "R4") (pin "2") (pinfunction "2_2") (pintype "passive"))
      (node (ref "R5") (pin "2") (pinfunction "2_2") (pintype "passive"))
      (node (ref "R7") (pin "2") (pinfunction "2_2") (pintype "passive"))
      (node (ref "R9") (pin "2") (pinfunction "2_2") (pintype "passive"))
    )
    (net (code "39") (name "unconnected-(IC1-1Q-Pad3)") (class "Default")
      (node (ref "IC1") (pin "3") (pinfunction "1Q_3") (pintype "bidirectional"))
    )
    (net (code "40") (name "unconnected-(IC1-2Q-Pad5)") (class "Default")
      (node (ref "IC1") (pin "5") (pinfunction "2Q_5") (pintype "bidirectional"))
    )
    (net (code "41") (name "unconnected-(IC2-1Q-Pad3)") (class "Default")
      (node (ref "IC2") (pin "3") (pinfunction "1Q_3") (pintype "bidirectional"))
    )
    (net (code "42") (name "unconnected-(IC2-2Q-Pad5)") (class "Default")
      (node (ref "IC2") (pin "5") (pinfunction "2Q_5") (pintype "bidirectional"))
    )
    (net (code "43") (name "unconnected-(IC3-1Q-Pad3)") (class "Default")
      (node (ref "IC3") (pin "3") (pinfunction "1Q_3") (pintype "bidirectional"))
    )
    (net (code "44") (name "unconnected-(IC3-2Q-Pad5)") (class "Default")
      (node (ref "IC3") (pin "5") (pinfunction "2Q_5") (pintype "bidirectional"))
    )
    (net (code "45") (name "unconnected-(IC4-1Q-Pad3)") (class "Default")
      (node (ref "IC4") (pin "3") (pinfunction "1Q_3") (pintype "bidirectional"))
    )
    (net (code "46") (name "unconnected-(IC4-2Q-Pad5)") (class "Default")
      (node (ref "IC4") (pin "5") (pinfunction "2Q_5") (pintype "bidirectional"))
    )
    (net (code "47") (name "unconnected-(MP1-P$1-Pad1)") (class "Default")
      (node (ref "MP1") (pin "1") (pinfunction "P$1_1") (pintype "passive"))
    )
    (net (code "48") (name "unconnected-(MP2-P$1-Pad1)") (class "Default")
      (node (ref "MP2") (pin "1") (pinfunction "P$1_1") (pintype "passive"))
    )
    (net (code "49") (name "unconnected-(MP3-P$1-Pad1)") (class "Default")
      (node (ref "MP3") (pin "1") (pinfunction "P$1_1") (pintype "passive"))
    )
    (net (code "50") (name "unconnected-(MP4-P$1-Pad1)") (class "Default")
      (node (ref "MP4") (pin "1") (pinfunction "P$1_1") (pintype "passive"))
    )
    (net (code "51") (name "unconnected-(PAD17-P-Pad1)") (class "Default")
      (node (ref "PAD17") (pin "1") (pinfunction "P_1") (pintype "passive"))
    )
    (net (code "52") (name "unconnected-(PAD18-P-Pad1)") (class "Default")
      (node (ref "PAD18") (pin "1") (pinfunction "P_1") (pintype "passive"))
    )
    (net (code "53") (name "unconnected-(S1-PadMH1)") (class "Default")
      (node (ref "S1") (pin "MH1") (pinfunction "MH1_MH1") (pintype "bidirectional"))
    )
    (net (code "54") (name "unconnected-(S1-PadMH2)") (class "Default")
      (node (ref "S1") (pin "MH2") (pinfunction "MH2_MH2") (pintype "bidirectional"))
    )
    (net (code "55") (name "unconnected-(S2-PadMH1)") (class "Default")
      (node (ref "S2") (pin "MH1") (pinfunction "MH1_MH1") (pintype "bidirectional"))
    )
    (net (code "56") (name "unconnected-(S2-PadMH2)") (class "Default")
      (node (ref "S2") (pin "MH2") (pinfunction "MH2_MH2") (pintype "bidirectional"))
    )
    (net (code "57") (name "unconnected-(S3-PadMH1)") (class "Default")
      (node (ref "S3") (pin "MH1") (pinfunction "MH1_MH1") (pintype "bidirectional"))
    )
    (net (code "58") (name "unconnected-(S3-PadMH2)") (class "Default")
      (node (ref "S3") (pin "MH2") (pinfunction "MH2_MH2") (pintype "bidirectional"))
    )
    (net (code "59") (name "unconnected-(S4-PadMH1)") (class "Default")
      (node (ref "S4") (pin "MH1") (pinfunction "MH1_MH1") (pintype "bidirectional"))
    )
    (net (code "60") (name "unconnected-(S4-PadMH2)") (class "Default")
      (node (ref "S4") (pin "MH2") (pinfunction "MH2_MH2") (pintype "bidirectional"))
    )
    (net (code "61") (name "unconnected-(S5-Pad1)") (class "Default")
      (node (ref "S5") (pin "1") (pinfunction "1_1") (pintype "bidirectional"))
    )
    (net (code "62") (name "unconnected-(S5-Pad2)") (class "Default")
      (node (ref "S5") (pin "2") (pinfunction "2_2") (pintype "bidirectional"))
    )
    (net (code "63") (name "unconnected-(S5-PadMH1)") (class "Default")
      (node (ref "S5") (pin "MH1") (pinfunction "MH1_MH1") (pintype "bidirectional"))
    )
    (net (code "64") (name "unconnected-(S5-PadMH2)") (class "Default")
      (node (ref "S5") (pin "MH2") (pinfunction "MH2_MH2") (pintype "bidirectional"))
    )
    (net (code "65") (name "unconnected-(S6-PadMH1)") (class "Default")
      (node (ref "S6") (pin "MH1") (pinfunction "MH1_MH1") (pintype "bidirectional"))
    )
    (net (code "66") (name "unconnected-(S6-PadMH2)") (class "Default")
      (node (ref "S6") (pin "MH2") (pinfunction "MH2_MH2") (pintype "bidirectional"))
    )
    (net (code "67") (name "unconnected-(S7-PadMH1)") (class "Default")
      (node (ref "S7") (pin "MH1") (pinfunction "MH1_MH1") (pintype "bidirectional"))
    )
    (net (code "68") (name "unconnected-(S7-PadMH2)") (class "Default")
      (node (ref "S7") (pin "MH2") (pinfunction "MH2_MH2") (pintype "bidirectional"))
    )
    (net (code "69") (name "unconnected-(S8-PadMH1)") (class "Default")
      (node (ref "S8") (pin "MH1") (pinfunction "MH1_MH1") (pintype "bidirectional"))
    )
    (net (code "70") (name "unconnected-(S8-PadMH2)") (class "Default")
      (node (ref "S8") (pin "MH2") (pinfunction "MH2_MH2") (pintype "bidirectional"))
    )
    (net (code "71") (name "unconnected-(S9-PadMH1)") (class "Default")
      (node (ref "S9") (pin "MH1") (pinfunction "MH1_MH1") (pintype "bidirectional"))
    )
    (net (code "72") (name "unconnected-(S9-PadMH2)") (class "Default")
      (node (ref "S9") (pin "MH2") (pinfunction "MH2_MH2") (pintype "bidirectional"))
    )
  )
)
